# s3-pilot2.net
KiCad netlist of a schematic drawn in EAGLE
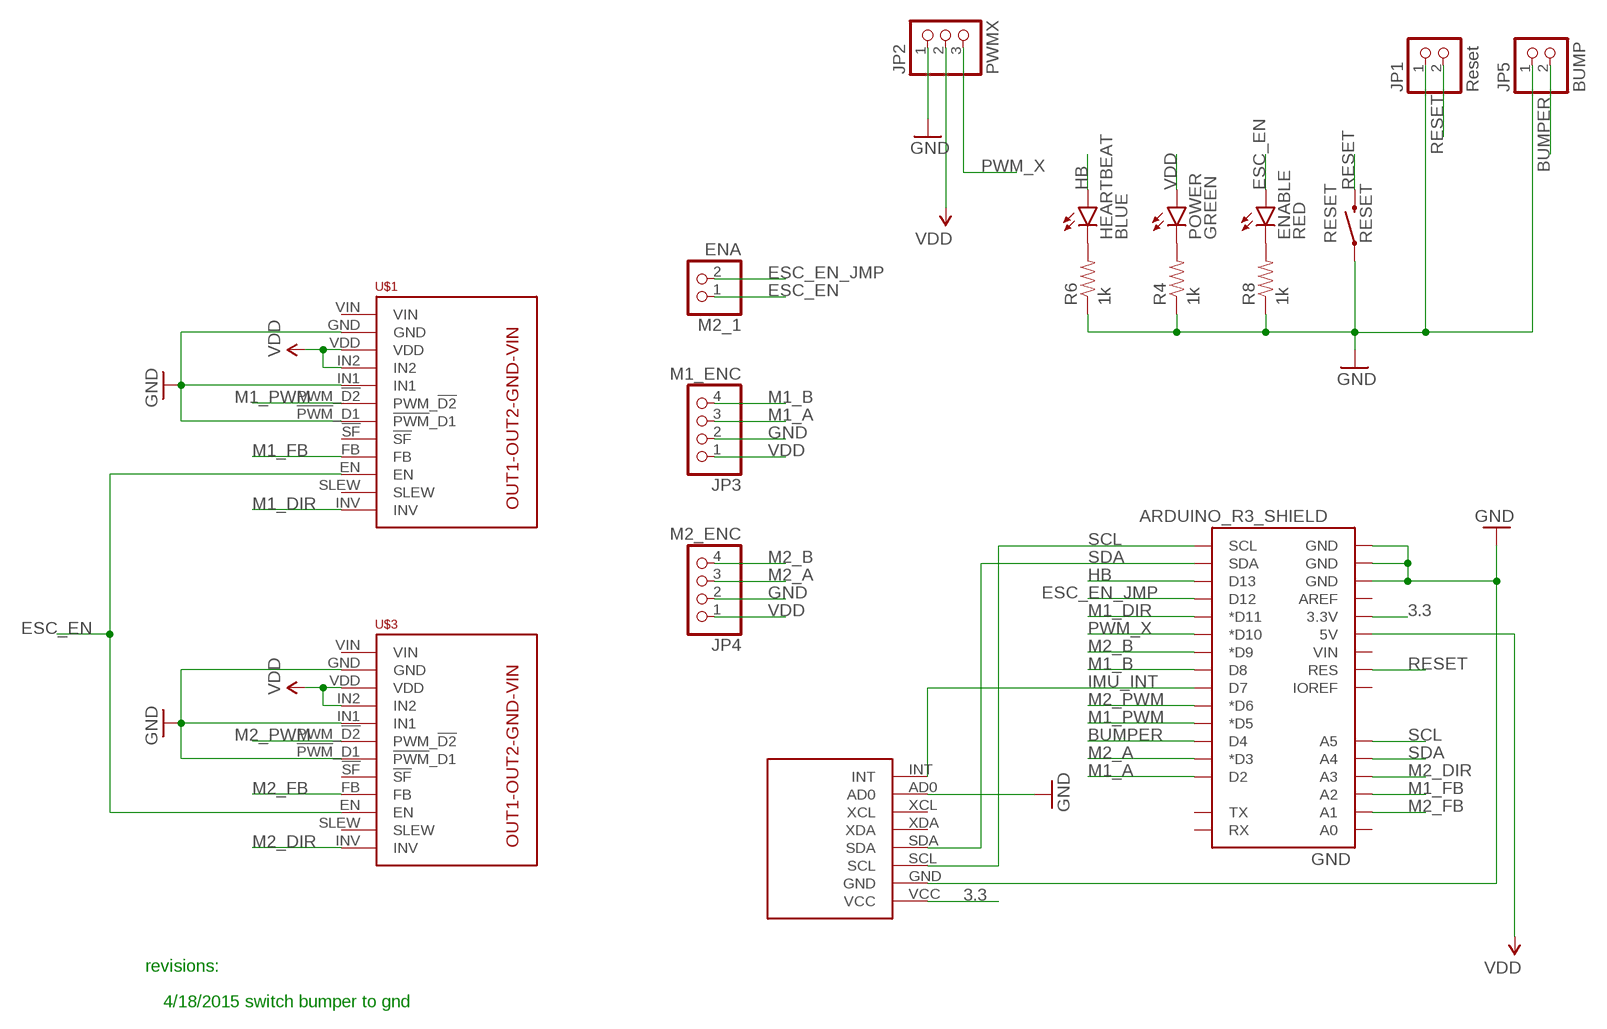
[diagram p0: schematic, sheet 1]

(export (version "E")
  (design (tool "Eeschema 10.0.6"))
  (components
    (comp (ref "ENABLE")
      (value "RED")
      (footprint "eagle-import:LED-1206")
      (libsource (lib "eagle-import") (part "LED-RED1206"))
    )
    (comp (ref "GND")
      (value "ARDUINO_R3_SHIELD")
      (footprint "eagle-import:UNO_R3_SHIELD")
      (libsource (lib "eagle-import") (part "ARDUINO_R3_SHIELD"))
    )
    (comp (ref "HEARTBEAT")
      (value "BLUE")
      (footprint "eagle-import:LED-1206")
      (libsource (lib "eagle-import") (part "LED-BLUE1206"))
    )
    (comp (ref "JP1")
      (value "Reset")
      (footprint "eagle-import:1X02")
      (libsource (lib "eagle-import") (part "PINHD-1X2"))
    )
    (comp (ref "JP2")
      (value "PWMX")
      (footprint "eagle-import:1X03_90")
      (libsource (lib "eagle-import") (part "PINHD-1X3/90"))
    )
    (comp (ref "JP3")
      (value "M1_ENC")
      (footprint "eagle-import:1X04_90")
      (libsource (lib "eagle-import") (part "PINHD-1X4/90"))
    )
    (comp (ref "JP4")
      (value "M2_ENC")
      (footprint "eagle-import:1X04_90")
      (libsource (lib "eagle-import") (part "PINHD-1X4/90"))
    )
    (comp (ref "JP5")
      (value "BUMP")
      (footprint "eagle-import:1X02_90")
      (libsource (lib "eagle-import") (part "PINHD-1X2/90"))
    )
    (comp (ref "M2_1")
      (value "ENA")
      (footprint "eagle-import:1X02")
      (libsource (lib "eagle-import") (part "PINHD-1X2"))
    )
    (comp (ref "MPU6050")
      (value "MPU-6050-BO")
      (footprint "eagle-import:MPU-6050-BO")
      (libsource (lib "eagle-import") (part "MPU-6050-BO"))
    )
    (comp (ref "POWER")
      (value "GREEN")
      (footprint "eagle-import:LED-1206")
      (libsource (lib "eagle-import") (part "LED-GREENLARGE"))
    )
    (comp (ref "R4")
      (value "1k")
      (footprint "eagle-import:1206")
      (libsource (lib "eagle-import") (part "RESISTOR1206"))
    )
    (comp (ref "R6")
      (value "1k")
      (footprint "eagle-import:1206")
      (libsource (lib "eagle-import") (part "RESISTOR1206"))
    )
    (comp (ref "R8")
      (value "1k")
      (footprint "eagle-import:1206")
      (libsource (lib "eagle-import") (part "RESISTOR1206"))
    )
    (comp (ref "RESET")
      (value "RESET")
      (footprint "eagle-import:TACTILE_SWITCH_TALL")
      (libsource (lib "eagle-import") (part "SWITCH-MOMENTARY-2SMD-4"))
    )
    (comp (ref "U$1")
      (value "M1")
      (footprint "eagle-import:MC33926-SINGLE-BO")
      (libsource (lib "eagle-import") (part "MC33926-SINGLE-BO"))
    )
    (comp (ref "U$3")
      (value "M2")
      (footprint "eagle-import:MC33926-SINGLE-BO")
      (libsource (lib "eagle-import") (part "MC33926-SINGLE-BO"))
    )
  )
  (nets
    (net (code "1") (name "/3.3") (class "Default")
      (node (ref "GND") (pin "3.3V") (pinfunction "3.3V_3.3V") (pintype "bidirectional"))
      (node (ref "MPU6050") (pin "VCC") (pinfunction "VCC_VCC") (pintype "power_in"))
    )
    (net (code "2") (name "/BUMPER") (class "Default")
      (node (ref "GND") (pin "D4") (pinfunction "D4_D4") (pintype "bidirectional"))
      (node (ref "JP5") (pin "2") (pinfunction "2_2") (pintype "passive"))
    )
    (net (code "3") (name "/ESC_EN") (class "Default")
      (node (ref "ENABLE") (pin "A") (pinfunction "A_A") (pintype "passive"))
      (node (ref "M2_1") (pin "1") (pinfunction "1_1") (pintype "passive"))
      (node (ref "U$1") (pin "EN") (pinfunction "EN_EN") (pintype "input"))
      (node (ref "U$3") (pin "EN") (pinfunction "EN_EN") (pintype "input"))
    )
    (net (code "4") (name "/ESC_EN_JMP") (class "Default")
      (node (ref "GND") (pin "D12") (pinfunction "D12_D12") (pintype "bidirectional"))
      (node (ref "M2_1") (pin "2") (pinfunction "2_2") (pintype "passive"))
    )
    (net (code "5") (name "/HB") (class "Default")
      (node (ref "GND") (pin "D13") (pinfunction "D13_D13") (pintype "bidirectional"))
      (node (ref "HEARTBEAT") (pin "A") (pinfunction "A_A") (pintype "passive"))
    )
    (net (code "6") (name "/IMU_INT") (class "Default")
      (node (ref "GND") (pin "D7") (pinfunction "D7_D7") (pintype "bidirectional"))
      (node (ref "MPU6050") (pin "INT") (pinfunction "INT_INT") (pintype "output"))
    )
    (net (code "7") (name "/M1_A") (class "Default")
      (node (ref "GND") (pin "D2") (pinfunction "D2_D2") (pintype "bidirectional"))
      (node (ref "JP3") (pin "3") (pinfunction "3_3") (pintype "passive"))
    )
    (net (code "8") (name "/M1_B") (class "Default")
      (node (ref "GND") (pin "D8") (pinfunction "D8_D8") (pintype "bidirectional"))
      (node (ref "JP3") (pin "4") (pinfunction "4_4") (pintype "passive"))
    )
    (net (code "9") (name "/M1_DIR") (class "Default")
      (node (ref "GND") (pin "D11") (pinfunction "*D11_D11") (pintype "bidirectional"))
      (node (ref "U$1") (pin "INV") (pinfunction "INV_INV") (pintype "input"))
    )
    (net (code "10") (name "/M1_FB") (class "Default")
      (node (ref "GND") (pin "A2") (pinfunction "A2_A2") (pintype "bidirectional"))
      (node (ref "U$1") (pin "FB") (pinfunction "FB_FB") (pintype "output"))
    )
    (net (code "11") (name "/M1_PWM") (class "Default")
      (node (ref "GND") (pin "D5") (pinfunction "*D5_D5") (pintype "bidirectional"))
      (node (ref "U$1") (pin "PWM_!D2") (pinfunction "PWM_~{D2}_PWM_!D2") (pintype "input"))
    )
    (net (code "12") (name "/M2_A") (class "Default")
      (node (ref "GND") (pin "D3") (pinfunction "*D3_D3") (pintype "bidirectional"))
      (node (ref "JP4") (pin "3") (pinfunction "3_3") (pintype "passive"))
    )
    (net (code "13") (name "/M2_B") (class "Default")
      (node (ref "GND") (pin "D9") (pinfunction "*D9_D9") (pintype "bidirectional"))
      (node (ref "JP4") (pin "4") (pinfunction "4_4") (pintype "passive"))
    )
    (net (code "14") (name "/M2_DIR") (class "Default")
      (node (ref "GND") (pin "A3") (pinfunction "A3_A3") (pintype "bidirectional"))
      (node (ref "U$3") (pin "INV") (pinfunction "INV_INV") (pintype "input"))
    )
    (net (code "15") (name "/M2_FB") (class "Default")
      (node (ref "GND") (pin "A1") (pinfunction "A1_A1") (pintype "bidirectional"))
      (node (ref "U$3") (pin "FB") (pinfunction "FB_FB") (pintype "output"))
    )
    (net (code "16") (name "/M2_PWM") (class "Default")
      (node (ref "GND") (pin "D6") (pinfunction "*D6_D6") (pintype "bidirectional"))
      (node (ref "U$3") (pin "PWM_!D2") (pinfunction "PWM_~{D2}_PWM_!D2") (pintype "input"))
    )
    (net (code "17") (name "/PWM_X") (class "Default")
      (node (ref "GND") (pin "D10") (pinfunction "*D10_D10") (pintype "bidirectional"))
      (node (ref "JP2") (pin "3") (pinfunction "3_3") (pintype "passive"))
    )
    (net (code "18") (name "/RESET") (class "Default")
      (node (ref "GND") (pin "RES") (pinfunction "RES_RES") (pintype "bidirectional"))
      (node (ref "JP1") (pin "2") (pinfunction "2_2") (pintype "passive"))
      (node (ref "RESET") (pin "B2") (pinfunction "2_B2") (pintype "passive"))
    )
    (net (code "19") (name "/SCL") (class "Default")
      (node (ref "GND") (pin "A5") (pinfunction "A5_A5") (pintype "bidirectional"))
      (node (ref "GND") (pin "SCL") (pinfunction "SCL_SCL") (pintype "bidirectional"))
      (node (ref "MPU6050") (pin "SCL") (pinfunction "SCL_SCL") (pintype "bidirectional"))
    )
    (net (code "20") (name "/SDA") (class "Default")
      (node (ref "GND") (pin "A4") (pinfunction "A4_A4") (pintype "bidirectional"))
      (node (ref "GND") (pin "SDA") (pinfunction "SDA_SDA") (pintype "bidirectional"))
      (node (ref "MPU6050") (pin "SDA") (pinfunction "SDA_SDA") (pintype "bidirectional"))
    )
    (net (code "21") (name "GND") (class "Default")
      (node (ref "GND") (pin "GND@0") (pinfunction "GND_GND@0") (pintype "bidirectional"))
      (node (ref "GND") (pin "GND@1") (pinfunction "GND_GND@1") (pintype "bidirectional"))
      (node (ref "GND") (pin "GND@2") (pinfunction "GND_GND@2") (pintype "bidirectional"))
      (node (ref "JP1") (pin "1") (pinfunction "1_1") (pintype "passive"))
      (node (ref "JP2") (pin "1") (pinfunction "1_1") (pintype "passive"))
      (node (ref "JP3") (pin "2") (pinfunction "2_2") (pintype "passive"))
      (node (ref "JP4") (pin "2") (pinfunction "2_2") (pintype "passive"))
      (node (ref "JP5") (pin "1") (pinfunction "1_1") (pintype "passive"))
      (node (ref "MPU6050") (pin "AD0") (pinfunction "AD0_AD0") (pintype "input"))
      (node (ref "MPU6050") (pin "GND") (pinfunction "GND_GND") (pintype "power_in"))
      (node (ref "R4") (pin "1") (pinfunction "1_1") (pintype "passive"))
      (node (ref "R6") (pin "1") (pinfunction "1_1") (pintype "passive"))
      (node (ref "R8") (pin "1") (pinfunction "1_1") (pintype "passive"))
      (node (ref "RESET") (pin "A2") (pinfunction "1_A2") (pintype "passive"))
      (node (ref "U$1") (pin "!PWM!_D1") (pinfunction "~{PWM}_D1_!PWM!_D1") (pintype "input"))
      (node (ref "U$1") (pin "GND") (pinfunction "GND_GND") (pintype "power_in"))
      (node (ref "U$1") (pin "IN1") (pinfunction "IN1_IN1") (pintype "input"))
      (node (ref "U$3") (pin "!PWM!_D1") (pinfunction "~{PWM}_D1_!PWM!_D1") (pintype "input"))
      (node (ref "U$3") (pin "GND") (pinfunction "GND_GND") (pintype "power_in"))
      (node (ref "U$3") (pin "IN1") (pinfunction "IN1_IN1") (pintype "input"))
    )
    (net (code "22") (name "Net-(ENABLE-PadC)") (class "Default")
      (node (ref "ENABLE") (pin "C") (pinfunction "C_C") (pintype "passive"))
      (node (ref "R8") (pin "2") (pinfunction "2_2") (pintype "passive"))
    )
    (net (code "23") (name "Net-(HEARTBEAT-PadC)") (class "Default")
      (node (ref "HEARTBEAT") (pin "C") (pinfunction "C_C") (pintype "passive"))
      (node (ref "R6") (pin "2") (pinfunction "2_2") (pintype "passive"))
    )
    (net (code "24") (name "Net-(POWER-PadC)") (class "Default")
      (node (ref "POWER") (pin "C") (pinfunction "C_C") (pintype "passive"))
      (node (ref "R4") (pin "2") (pinfunction "2_2") (pintype "passive"))
    )
    (net (code "25") (name "VDD") (class "Default")
      (node (ref "GND") (pin "5V") (pinfunction "5V_5V") (pintype "bidirectional"))
      (node (ref "JP2") (pin "2") (pinfunction "2_2") (pintype "passive"))
      (node (ref "JP3") (pin "1") (pinfunction "1_1") (pintype "passive"))
      (node (ref "JP4") (pin "1") (pinfunction "1_1") (pintype "passive"))
      (node (ref "POWER") (pin "A") (pinfunction "A_A") (pintype "passive"))
      (node (ref "U$1") (pin "IN2") (pinfunction "IN2_IN2") (pintype "input"))
      (node (ref "U$1") (pin "VDD") (pinfunction "VDD_VDD") (pintype "power_in"))
      (node (ref "U$3") (pin "IN2") (pinfunction "IN2_IN2") (pintype "input"))
      (node (ref "U$3") (pin "VDD") (pinfunction "VDD_VDD") (pintype "power_in"))
    )
    (net (code "26") (name "unconnected-(GND-PadA0)") (class "Default")
      (node (ref "GND") (pin "A0") (pinfunction "A0_A0") (pintype "bidirectional"))
    )
    (net (code "27") (name "unconnected-(GND-PadAREF)") (class "Default")
      (node (ref "GND") (pin "AREF") (pinfunction "AREF_AREF") (pintype "bidirectional"))
    )
    (net (code "28") (name "unconnected-(GND-PadIOREF)") (class "Default")
      (node (ref "GND") (pin "IOREF") (pinfunction "IOREF_IOREF") (pintype "bidirectional"))
    )
    (net (code "29") (name "unconnected-(GND-PadRX)") (class "Default")
      (node (ref "GND") (pin "RX") (pinfunction "RX_RX") (pintype "bidirectional"))
    )
    (net (code "30") (name "unconnected-(GND-PadTX)") (class "Default")
      (node (ref "GND") (pin "TX") (pinfunction "TX_TX") (pintype "bidirectional"))
    )
    (net (code "31") (name "unconnected-(GND-PadVIN)") (class "Default")
      (node (ref "GND") (pin "VIN") (pinfunction "VIN_VIN") (pintype "bidirectional"))
    )
    (net (code "32") (name "unconnected-(MPU6050-PadXCL)") (class "Default")
      (node (ref "MPU6050") (pin "XCL") (pinfunction "XCL_XCL") (pintype "bidirectional"))
    )
    (net (code "33") (name "unconnected-(MPU6050-PadXDA)") (class "Default")
      (node (ref "MPU6050") (pin "XDA") (pinfunction "XDA_XDA") (pintype "bidirectional"))
    )
    (net (code "34") (name "unconnected-(U$1-PadSLEW)") (class "Default")
      (node (ref "U$1") (pin "SLEW") (pinfunction "SLEW_SLEW") (pintype "input"))
    )
    (net (code "35") (name "unconnected-(U$1-PadVIN)") (class "Default")
      (node (ref "U$1") (pin "VIN") (pinfunction "VIN_VIN") (pintype "no_connect"))
    )
    (net (code "36") (name "unconnected-(U$1-~{SF}-Pad!SF)") (class "Default")
      (node (ref "U$1") (pin "!SF") (pinfunction "~{SF}_!SF") (pintype "output"))
    )
    (net (code "37") (name "unconnected-(U$3-PadSLEW)") (class "Default")
      (node (ref "U$3") (pin "SLEW") (pinfunction "SLEW_SLEW") (pintype "input"))
    )
    (net (code "38") (name "unconnected-(U$3-PadVIN)") (class "Default")
      (node (ref "U$3") (pin "VIN") (pinfunction "VIN_VIN") (pintype "no_connect"))
    )
    (net (code "39") (name "unconnected-(U$3-~{SF}-Pad!SF)") (class "Default")
      (node (ref "U$3") (pin "!SF") (pinfunction "~{SF}_!SF") (pintype "output"))
    )
  )
)
